# HBPB_FM_v4.net
KiCad netlist of a schematic drawn in EAGLE
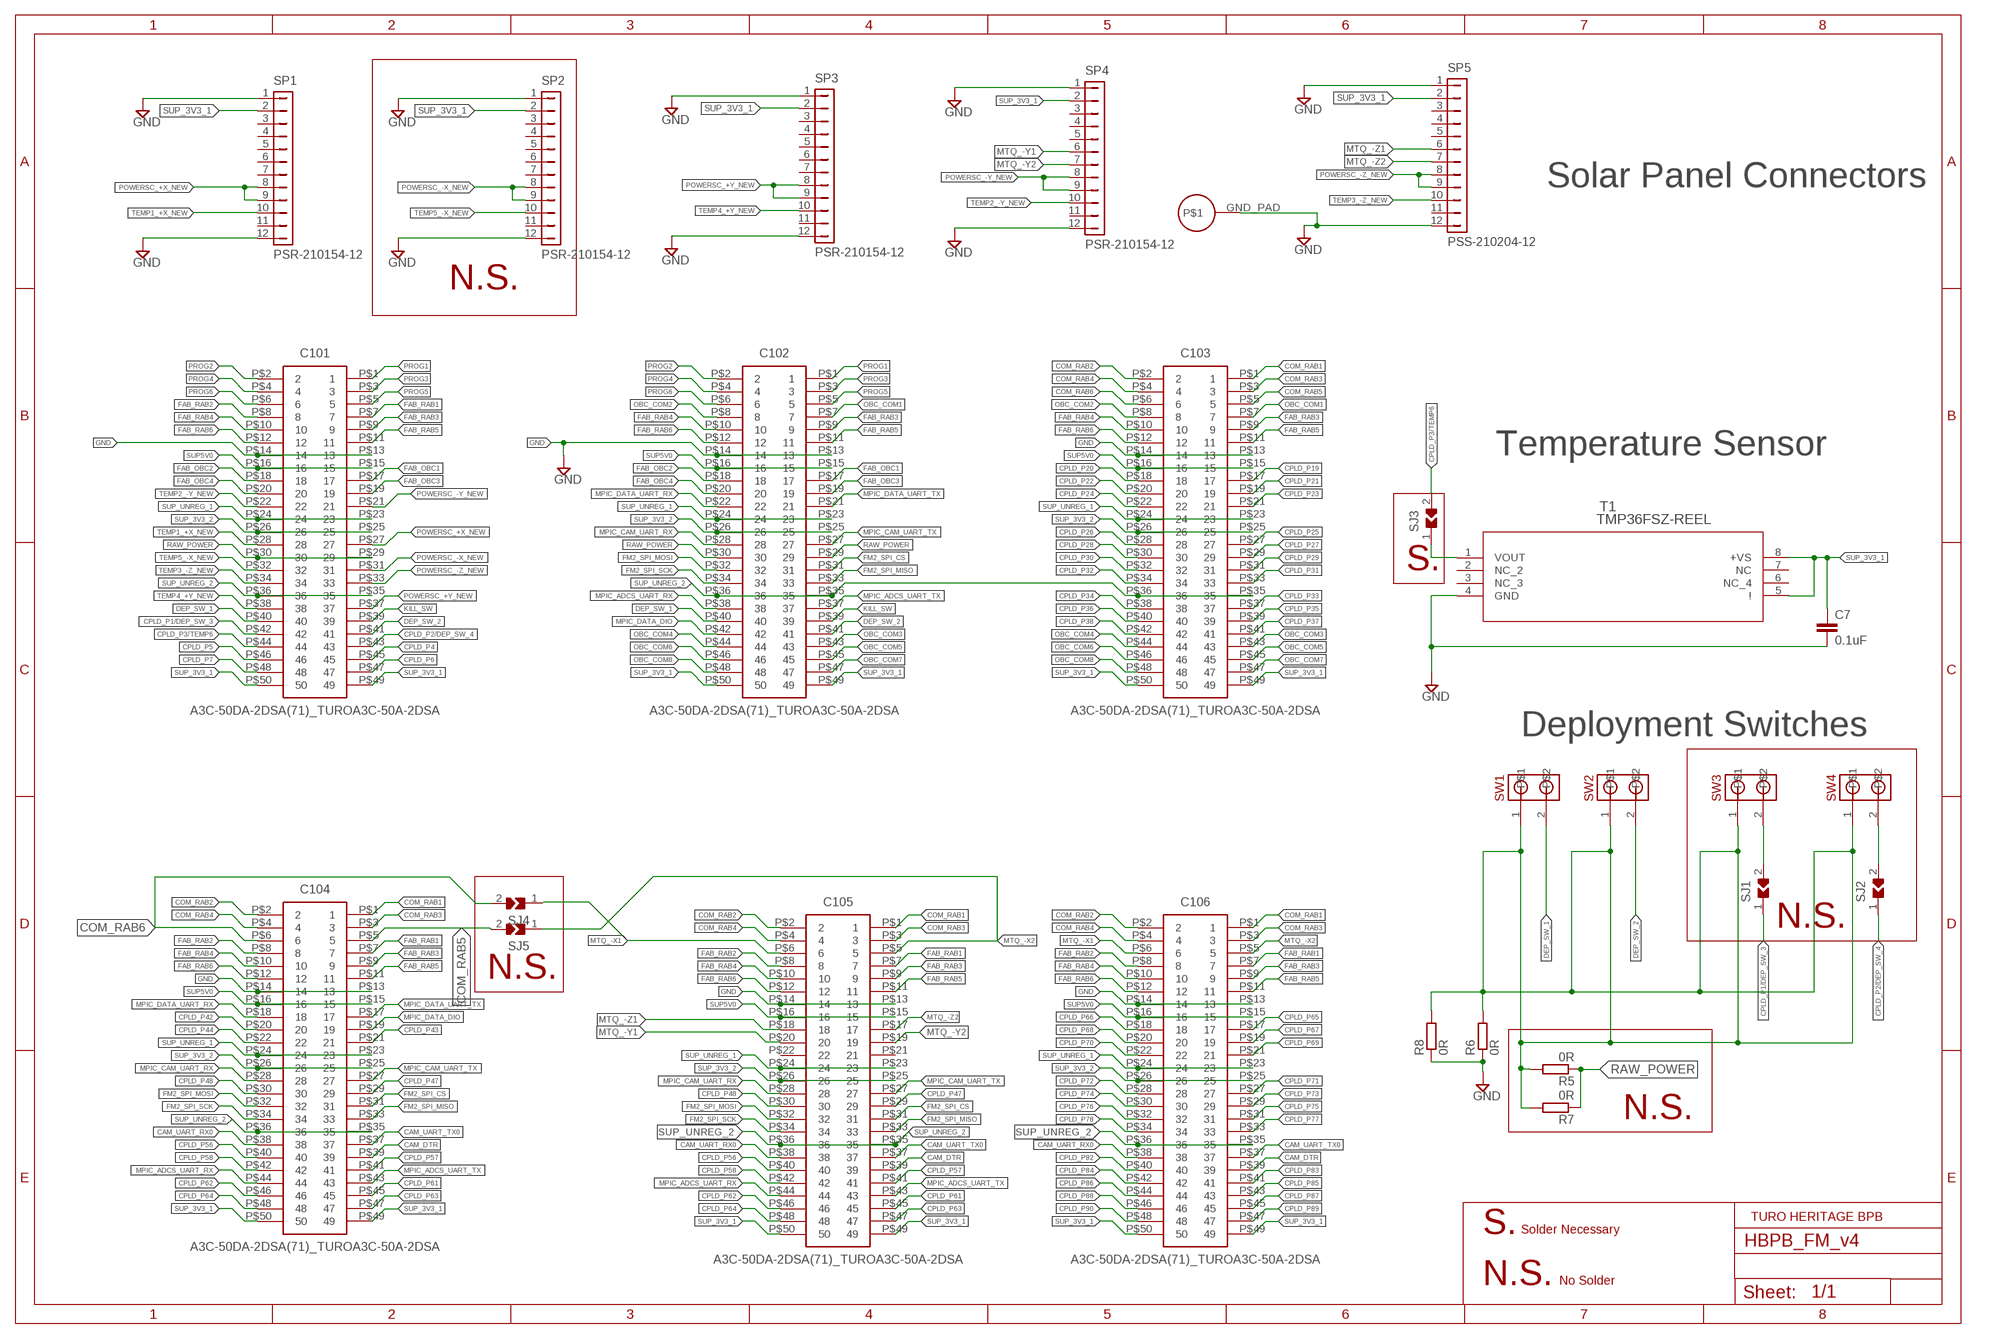
[diagram p0: schematic, sheet 1]

(export (version "E")
  (design (tool "Eeschema 10.0.6"))
  (components
    (comp (ref "C7")
      (value "0.1uF")
      (footprint "eagle-import:C0402")
      (libsource (lib "eagle-import") (part "CC0402"))
    )
    (comp (ref "C101")
      (value "A3C-50DA-2DSA(71)_TUROA3C-50A-2DSA")
      (footprint "eagle-import:SHDR50W60P200_2X25_5000X400X44_TR")
      (libsource (lib "eagle-import") (part "A3C-50DA-2DSA(71)_TUROA3C-50A-2DSA"))
    )
    (comp (ref "C102")
      (value "A3C-50DA-2DSA(71)_TUROA3C-50A-2DSA")
      (footprint "eagle-import:SHDR50W60P200_2X25_5000X400X44_TR")
      (libsource (lib "eagle-import") (part "A3C-50DA-2DSA(71)_TUROA3C-50A-2DSA"))
    )
    (comp (ref "C103")
      (value "A3C-50DA-2DSA(71)_TUROA3C-50A-2DSA")
      (footprint "eagle-import:SHDR50W60P200_2X25_5000X400X44_TR")
      (libsource (lib "eagle-import") (part "A3C-50DA-2DSA(71)_TUROA3C-50A-2DSA"))
    )
    (comp (ref "C104")
      (value "A3C-50DA-2DSA(71)_TUROA3C-50A-2DSA")
      (footprint "eagle-import:SHDR50W60P200_2X25_5000X400X44_TR")
      (libsource (lib "eagle-import") (part "A3C-50DA-2DSA(71)_TUROA3C-50A-2DSA"))
    )
    (comp (ref "C105")
      (value "A3C-50DA-2DSA(71)_TUROA3C-50A-2DSA")
      (footprint "eagle-import:SHDR50W60P200_2X25_5000X400X44_TR")
      (libsource (lib "eagle-import") (part "A3C-50DA-2DSA(71)_TUROA3C-50A-2DSA"))
    )
    (comp (ref "C106")
      (value "A3C-50DA-2DSA(71)_TUROA3C-50A-2DSA")
      (footprint "eagle-import:SHDR50W60P200_2X25_5000X400X44_TR")
      (libsource (lib "eagle-import") (part "A3C-50DA-2DSA(71)_TUROA3C-50A-2DSA"))
    )
    (comp (ref "R5")
      (value "0R")
      (footprint "eagle-import:R3216")
      (libsource (lib "eagle-import") (part "RR3216"))
    )
    (comp (ref "R6")
      (value "0R")
      (footprint "eagle-import:R3216")
      (libsource (lib "eagle-import") (part "RR3216"))
    )
    (comp (ref "R7")
      (value "0R")
      (footprint "eagle-import:R3216")
      (libsource (lib "eagle-import") (part "RR3216"))
    )
    (comp (ref "R8")
      (value "0R")
      (footprint "eagle-import:R3216")
      (libsource (lib "eagle-import") (part "RR3216"))
    )
    (comp (ref "SJ1")
      (value "SJ_BY_TURO")
      (footprint "eagle-import:SJ_TURO")
      (libsource (lib "eagle-import") (part "SJ_BY_TURO"))
    )
    (comp (ref "SJ2")
      (value "0R")
      (footprint "eagle-import:SJ_TURO")
      (libsource (lib "eagle-import") (part "SJ_BY_TURO"))
    )
    (comp (ref "SJ3")
      (value "SJ_BY_TURO")
      (footprint "eagle-import:SJ_TURO")
      (libsource (lib "eagle-import") (part "SJ_BY_TURO"))
    )
    (comp (ref "SJ4")
      (value "SJ_BY_TURO")
      (footprint "eagle-import:SJ_TURO")
      (libsource (lib "eagle-import") (part "SJ_BY_TURO"))
    )
    (comp (ref "SJ5")
      (value "SJ_BY_TURO")
      (footprint "eagle-import:SJ_TURO")
      (libsource (lib "eagle-import") (part "SJ_BY_TURO"))
    )
    (comp (ref "SP1")
      (value "PSR-210154-12")
      (footprint "eagle-import:PIN1X12_90")
      (libsource (lib "eagle-import") (part "PSR-210154-12"))
    )
    (comp (ref "SP2")
      (value "PSR-210154-12")
      (footprint "eagle-import:PIN1X12_90")
      (libsource (lib "eagle-import") (part "PSR-210154-12"))
    )
    (comp (ref "SP3")
      (value "PSR-210154-12")
      (footprint "eagle-import:PIN1X12_90")
      (libsource (lib "eagle-import") (part "PSR-210154-12"))
    )
    (comp (ref "SP4")
      (value "PSR-210154-12")
      (footprint "eagle-import:PIN1X12_90")
      (libsource (lib "eagle-import") (part "PSR-210154-12"))
    )
    (comp (ref "SP5")
      (value "PSS-210204-12")
      (footprint "eagle-import:PIN1X12")
      (libsource (lib "eagle-import") (part "PSS-210204-12"))
    )
    (comp (ref "SW1")
      (value "MOLEX-CONN-2-0554600272")
      (footprint "eagle-import:MOLEX-CONN-2-BIRDS")
      (libsource (lib "eagle-import") (part "MOLEX-CONN-2-0554600272"))
    )
    (comp (ref "SW2")
      (value "MOLEX-CONN-2-0554600272")
      (footprint "eagle-import:MOLEX-CONN-2-BIRDS")
      (libsource (lib "eagle-import") (part "MOLEX-CONN-2-0554600272"))
    )
    (comp (ref "SW3")
      (value "MOLEX-CONN-2-0554600272")
      (footprint "eagle-import:MOLEX-CONN-2-BIRDS")
      (libsource (lib "eagle-import") (part "MOLEX-CONN-2-0554600272"))
    )
    (comp (ref "SW4")
      (value "MOLEX-CONN-2-0554600272")
      (footprint "eagle-import:MOLEX-CONN-2-BIRDS")
      (libsource (lib "eagle-import") (part "MOLEX-CONN-2-0554600272"))
    )
    (comp (ref "T1")
      (value "TMP36FSZ-REEL")
      (footprint "eagle-import:R_8")
      (fields (field (name "MANUFACTURER_PART_NUMBER") "TMP36FSZREEL"))
      (libsource (lib "eagle-import") (part "TMP36FSZ-REEL"))
    )
    (comp (ref "U$1")
      (value "GND_PAD")
      (footprint "eagle-import:GND_PAD")
      (libsource (lib "eagle-import") (part "GND_PAD"))
    )
  )
  (nets
    (net (code "1") (name "CAM_DTR") (class "Default")
      (node (ref "C104") (pin "P$39") (pinfunction "39_P$39") (pintype "passive"))
      (node (ref "C105") (pin "P$39") (pinfunction "39_P$39") (pintype "passive"))
      (node (ref "C106") (pin "P$39") (pinfunction "39_P$39") (pintype "passive"))
    )
    (net (code "2") (name "CAM_UART_RX0") (class "Default")
      (node (ref "C104") (pin "P$38") (pinfunction "38_P$38") (pintype "passive"))
      (node (ref "C105") (pin "P$38") (pinfunction "38_P$38") (pintype "passive"))
      (node (ref "C106") (pin "P$38") (pinfunction "38_P$38") (pintype "passive"))
    )
    (net (code "3") (name "CAM_UART_TX0") (class "Default")
      (node (ref "C104") (pin "P$37") (pinfunction "37_P$37") (pintype "passive"))
      (node (ref "C105") (pin "P$37") (pinfunction "37_P$37") (pintype "passive"))
      (node (ref "C106") (pin "P$37") (pinfunction "37_P$37") (pintype "passive"))
    )
    (net (code "4") (name "COM_RAB1") (class "Default")
      (node (ref "C103") (pin "P$1") (pinfunction "1_P$1") (pintype "passive"))
      (node (ref "C104") (pin "P$1") (pinfunction "1_P$1") (pintype "passive"))
      (node (ref "C105") (pin "P$1") (pinfunction "1_P$1") (pintype "passive"))
      (node (ref "C106") (pin "P$1") (pinfunction "1_P$1") (pintype "passive"))
    )
    (net (code "5") (name "COM_RAB2") (class "Default")
      (node (ref "C103") (pin "P$2") (pinfunction "2_P$2") (pintype "passive"))
      (node (ref "C104") (pin "P$2") (pinfunction "2_P$2") (pintype "passive"))
      (node (ref "C105") (pin "P$2") (pinfunction "2_P$2") (pintype "passive"))
      (node (ref "C106") (pin "P$2") (pinfunction "2_P$2") (pintype "passive"))
    )
    (net (code "6") (name "COM_RAB3") (class "Default")
      (node (ref "C103") (pin "P$3") (pinfunction "3_P$3") (pintype "passive"))
      (node (ref "C104") (pin "P$3") (pinfunction "3_P$3") (pintype "passive"))
      (node (ref "C105") (pin "P$3") (pinfunction "3_P$3") (pintype "passive"))
      (node (ref "C106") (pin "P$3") (pinfunction "3_P$3") (pintype "passive"))
    )
    (net (code "7") (name "COM_RAB4") (class "Default")
      (node (ref "C103") (pin "P$4") (pinfunction "4_P$4") (pintype "passive"))
      (node (ref "C104") (pin "P$4") (pinfunction "4_P$4") (pintype "passive"))
      (node (ref "C105") (pin "P$4") (pinfunction "4_P$4") (pintype "passive"))
      (node (ref "C106") (pin "P$4") (pinfunction "4_P$4") (pintype "passive"))
    )
    (net (code "8") (name "COM_RAB5") (class "Default")
      (node (ref "C103") (pin "P$5") (pinfunction "5_P$5") (pintype "passive"))
      (node (ref "C104") (pin "P$5") (pinfunction "5_P$5") (pintype "passive"))
      (node (ref "SJ5") (pin "2") (pinfunction "2_2") (pintype "passive"))
    )
    (net (code "9") (name "COM_RAB6") (class "Default")
      (node (ref "C103") (pin "P$6") (pinfunction "6_P$6") (pintype "passive"))
      (node (ref "C104") (pin "P$6") (pinfunction "6_P$6") (pintype "passive"))
      (node (ref "SJ4") (pin "2") (pinfunction "2_2") (pintype "passive"))
    )
    (net (code "10") (name "CPLD_P1{slash}DEP_SW_3") (class "Default")
      (node (ref "C101") (pin "P$42") (pinfunction "42_P$42") (pintype "passive"))
      (node (ref "SJ1") (pin "1") (pinfunction "1_1") (pintype "passive"))
    )
    (net (code "11") (name "CPLD_P2{slash}DEP_SW_4") (class "Default")
      (node (ref "C101") (pin "P$43") (pinfunction "43_P$43") (pintype "passive"))
      (node (ref "SJ2") (pin "1") (pinfunction "1_1") (pintype "passive"))
    )
    (net (code "12") (name "CPLD_P3{slash}TEMP6") (class "Default")
      (node (ref "C101") (pin "P$44") (pinfunction "44_P$44") (pintype "passive"))
      (node (ref "SJ3") (pin "2") (pinfunction "2_2") (pintype "passive"))
    )
    (net (code "13") (name "CPLD_P4") (class "Default")
      (node (ref "C101") (pin "P$45") (pinfunction "45_P$45") (pintype "passive"))
    )
    (net (code "14") (name "CPLD_P5") (class "Default")
      (node (ref "C101") (pin "P$46") (pinfunction "46_P$46") (pintype "passive"))
    )
    (net (code "15") (name "CPLD_P6") (class "Default")
      (node (ref "C101") (pin "P$47") (pinfunction "47_P$47") (pintype "passive"))
    )
    (net (code "16") (name "CPLD_P7") (class "Default")
      (node (ref "C101") (pin "P$48") (pinfunction "48_P$48") (pintype "passive"))
    )
    (net (code "17") (name "CPLD_P19") (class "Default")
      (node (ref "C103") (pin "P$17") (pinfunction "17_P$17") (pintype "passive"))
    )
    (net (code "18") (name "CPLD_P20") (class "Default")
      (node (ref "C103") (pin "P$18") (pinfunction "18_P$18") (pintype "passive"))
    )
    (net (code "19") (name "CPLD_P21") (class "Default")
      (node (ref "C103") (pin "P$19") (pinfunction "19_P$19") (pintype "passive"))
    )
    (net (code "20") (name "CPLD_P22") (class "Default")
      (node (ref "C103") (pin "P$20") (pinfunction "20_P$20") (pintype "passive"))
    )
    (net (code "21") (name "CPLD_P23") (class "Default")
      (node (ref "C103") (pin "P$21") (pinfunction "21_P$21") (pintype "passive"))
    )
    (net (code "22") (name "CPLD_P24") (class "Default")
      (node (ref "C103") (pin "P$22") (pinfunction "22_P$22") (pintype "passive"))
    )
    (net (code "23") (name "CPLD_P25") (class "Default")
      (node (ref "C103") (pin "P$27") (pinfunction "27_P$27") (pintype "passive"))
    )
    (net (code "24") (name "CPLD_P26") (class "Default")
      (node (ref "C103") (pin "P$28") (pinfunction "28_P$28") (pintype "passive"))
    )
    (net (code "25") (name "CPLD_P27") (class "Default")
      (node (ref "C103") (pin "P$29") (pinfunction "29_P$29") (pintype "passive"))
    )
    (net (code "26") (name "CPLD_P28") (class "Default")
      (node (ref "C103") (pin "P$30") (pinfunction "30_P$30") (pintype "passive"))
    )
    (net (code "27") (name "CPLD_P29") (class "Default")
      (node (ref "C103") (pin "P$31") (pinfunction "31_P$31") (pintype "passive"))
    )
    (net (code "28") (name "CPLD_P30") (class "Default")
      (node (ref "C103") (pin "P$32") (pinfunction "32_P$32") (pintype "passive"))
    )
    (net (code "29") (name "CPLD_P31") (class "Default")
      (node (ref "C103") (pin "P$33") (pinfunction "33_P$33") (pintype "passive"))
    )
    (net (code "30") (name "CPLD_P32") (class "Default")
      (node (ref "C103") (pin "P$34") (pinfunction "34_P$34") (pintype "passive"))
    )
    (net (code "31") (name "CPLD_P33") (class "Default")
      (node (ref "C103") (pin "P$37") (pinfunction "37_P$37") (pintype "passive"))
    )
    (net (code "32") (name "CPLD_P34") (class "Default")
      (node (ref "C103") (pin "P$38") (pinfunction "38_P$38") (pintype "passive"))
    )
    (net (code "33") (name "CPLD_P35") (class "Default")
      (node (ref "C103") (pin "P$39") (pinfunction "39_P$39") (pintype "passive"))
    )
    (net (code "34") (name "CPLD_P36") (class "Default")
      (node (ref "C103") (pin "P$40") (pinfunction "40_P$40") (pintype "passive"))
    )
    (net (code "35") (name "CPLD_P37") (class "Default")
      (node (ref "C103") (pin "P$41") (pinfunction "41_P$41") (pintype "passive"))
    )
    (net (code "36") (name "CPLD_P38") (class "Default")
      (node (ref "C103") (pin "P$42") (pinfunction "42_P$42") (pintype "passive"))
    )
    (net (code "37") (name "CPLD_P42") (class "Default")
      (node (ref "C104") (pin "P$20") (pinfunction "20_P$20") (pintype "passive"))
    )
    (net (code "38") (name "CPLD_P43") (class "Default")
      (node (ref "C104") (pin "P$21") (pinfunction "21_P$21") (pintype "passive"))
    )
    (net (code "39") (name "CPLD_P44") (class "Default")
      (node (ref "C104") (pin "P$22") (pinfunction "22_P$22") (pintype "passive"))
    )
    (net (code "40") (name "CPLD_P47") (class "Default")
      (node (ref "C104") (pin "P$29") (pinfunction "29_P$29") (pintype "passive"))
      (node (ref "C105") (pin "P$29") (pinfunction "29_P$29") (pintype "passive"))
    )
    (net (code "41") (name "CPLD_P48") (class "Default")
      (node (ref "C104") (pin "P$30") (pinfunction "30_P$30") (pintype "passive"))
      (node (ref "C105") (pin "P$30") (pinfunction "30_P$30") (pintype "passive"))
    )
    (net (code "42") (name "CPLD_P56") (class "Default")
      (node (ref "C104") (pin "P$40") (pinfunction "40_P$40") (pintype "passive"))
      (node (ref "C105") (pin "P$40") (pinfunction "40_P$40") (pintype "passive"))
    )
    (net (code "43") (name "CPLD_P57") (class "Default")
      (node (ref "C104") (pin "P$41") (pinfunction "41_P$41") (pintype "passive"))
      (node (ref "C105") (pin "P$41") (pinfunction "41_P$41") (pintype "passive"))
    )
    (net (code "44") (name "CPLD_P58") (class "Default")
      (node (ref "C104") (pin "P$42") (pinfunction "42_P$42") (pintype "passive"))
      (node (ref "C105") (pin "P$42") (pinfunction "42_P$42") (pintype "passive"))
    )
    (net (code "45") (name "CPLD_P61") (class "Default")
      (node (ref "C104") (pin "P$45") (pinfunction "45_P$45") (pintype "passive"))
      (node (ref "C105") (pin "P$45") (pinfunction "45_P$45") (pintype "passive"))
    )
    (net (code "46") (name "CPLD_P62") (class "Default")
      (node (ref "C104") (pin "P$46") (pinfunction "46_P$46") (pintype "passive"))
      (node (ref "C105") (pin "P$46") (pinfunction "46_P$46") (pintype "passive"))
    )
    (net (code "47") (name "CPLD_P63") (class "Default")
      (node (ref "C104") (pin "P$47") (pinfunction "47_P$47") (pintype "passive"))
      (node (ref "C105") (pin "P$47") (pinfunction "47_P$47") (pintype "passive"))
    )
    (net (code "48") (name "CPLD_P64") (class "Default")
      (node (ref "C104") (pin "P$48") (pinfunction "48_P$48") (pintype "passive"))
      (node (ref "C105") (pin "P$48") (pinfunction "48_P$48") (pintype "passive"))
    )
    (net (code "49") (name "CPLD_P65") (class "Default")
      (node (ref "C106") (pin "P$17") (pinfunction "17_P$17") (pintype "passive"))
    )
    (net (code "50") (name "CPLD_P66") (class "Default")
      (node (ref "C106") (pin "P$18") (pinfunction "18_P$18") (pintype "passive"))
    )
    (net (code "51") (name "CPLD_P67") (class "Default")
      (node (ref "C106") (pin "P$19") (pinfunction "19_P$19") (pintype "passive"))
    )
    (net (code "52") (name "CPLD_P68") (class "Default")
      (node (ref "C106") (pin "P$20") (pinfunction "20_P$20") (pintype "passive"))
    )
    (net (code "53") (name "CPLD_P69") (class "Default")
      (node (ref "C106") (pin "P$21") (pinfunction "21_P$21") (pintype "passive"))
    )
    (net (code "54") (name "CPLD_P70") (class "Default")
      (node (ref "C106") (pin "P$22") (pinfunction "22_P$22") (pintype "passive"))
    )
    (net (code "55") (name "CPLD_P71") (class "Default")
      (node (ref "C106") (pin "P$27") (pinfunction "27_P$27") (pintype "passive"))
    )
    (net (code "56") (name "CPLD_P72") (class "Default")
      (node (ref "C106") (pin "P$28") (pinfunction "28_P$28") (pintype "passive"))
    )
    (net (code "57") (name "CPLD_P73") (class "Default")
      (node (ref "C106") (pin "P$29") (pinfunction "29_P$29") (pintype "passive"))
    )
    (net (code "58") (name "CPLD_P74") (class "Default")
      (node (ref "C106") (pin "P$30") (pinfunction "30_P$30") (pintype "passive"))
    )
    (net (code "59") (name "CPLD_P75") (class "Default")
      (node (ref "C106") (pin "P$31") (pinfunction "31_P$31") (pintype "passive"))
    )
    (net (code "60") (name "CPLD_P76") (class "Default")
      (node (ref "C106") (pin "P$32") (pinfunction "32_P$32") (pintype "passive"))
    )
    (net (code "61") (name "CPLD_P77") (class "Default")
      (node (ref "C106") (pin "P$33") (pinfunction "33_P$33") (pintype "passive"))
    )
    (net (code "62") (name "CPLD_P78") (class "Default")
      (node (ref "C106") (pin "P$34") (pinfunction "34_P$34") (pintype "passive"))
    )
    (net (code "63") (name "CPLD_P82") (class "Default")
      (node (ref "C106") (pin "P$40") (pinfunction "40_P$40") (pintype "passive"))
    )
    (net (code "64") (name "CPLD_P83") (class "Default")
      (node (ref "C106") (pin "P$41") (pinfunction "41_P$41") (pintype "passive"))
    )
    (net (code "65") (name "CPLD_P84") (class "Default")
      (node (ref "C106") (pin "P$42") (pinfunction "42_P$42") (pintype "passive"))
    )
    (net (code "66") (name "CPLD_P85") (class "Default")
      (node (ref "C106") (pin "P$43") (pinfunction "43_P$43") (pintype "passive"))
    )
    (net (code "67") (name "CPLD_P86") (class "Default")
      (node (ref "C106") (pin "P$44") (pinfunction "44_P$44") (pintype "passive"))
    )
    (net (code "68") (name "CPLD_P87") (class "Default")
      (node (ref "C106") (pin "P$45") (pinfunction "45_P$45") (pintype "passive"))
    )
    (net (code "69") (name "CPLD_P88") (class "Default")
      (node (ref "C106") (pin "P$46") (pinfunction "46_P$46") (pintype "passive"))
    )
    (net (code "70") (name "CPLD_P89") (class "Default")
      (node (ref "C106") (pin "P$47") (pinfunction "47_P$47") (pintype "passive"))
    )
    (net (code "71") (name "CPLD_P90") (class "Default")
      (node (ref "C106") (pin "P$48") (pinfunction "48_P$48") (pintype "passive"))
    )
    (net (code "72") (name "DEP_SW_1") (class "Default")
      (node (ref "C101") (pin "P$40") (pinfunction "40_P$40") (pintype "passive"))
      (node (ref "C102") (pin "P$40") (pinfunction "40_P$40") (pintype "passive"))
      (node (ref "SW1") (pin "2") (pinfunction "P$2_2") (pintype "bidirectional"))
    )
    (net (code "73") (name "DEP_SW_2") (class "Default")
      (node (ref "C101") (pin "P$41") (pinfunction "41_P$41") (pintype "passive"))
      (node (ref "C102") (pin "P$41") (pinfunction "41_P$41") (pintype "passive"))
      (node (ref "SW2") (pin "2") (pinfunction "P$2_2") (pintype "bidirectional"))
    )
    (net (code "74") (name "FAB_OBC1") (class "Default")
      (node (ref "C101") (pin "P$17") (pinfunction "17_P$17") (pintype "passive"))
      (node (ref "C102") (pin "P$17") (pinfunction "17_P$17") (pintype "passive"))
    )
    (net (code "75") (name "FAB_OBC2") (class "Default")
      (node (ref "C101") (pin "P$18") (pinfunction "18_P$18") (pintype "passive"))
      (node (ref "C102") (pin "P$18") (pinfunction "18_P$18") (pintype "passive"))
    )
    (net (code "76") (name "FAB_OBC3") (class "Default")
      (node (ref "C101") (pin "P$19") (pinfunction "19_P$19") (pintype "passive"))
      (node (ref "C102") (pin "P$19") (pinfunction "19_P$19") (pintype "passive"))
    )
    (net (code "77") (name "FAB_OBC4") (class "Default")
      (node (ref "C101") (pin "P$20") (pinfunction "20_P$20") (pintype "passive"))
      (node (ref "C102") (pin "P$20") (pinfunction "20_P$20") (pintype "passive"))
    )
    (net (code "78") (name "FAB_RAB1") (class "Default")
      (node (ref "C101") (pin "P$7") (pinfunction "7_P$7") (pintype "passive"))
      (node (ref "C104") (pin "P$7") (pinfunction "7_P$7") (pintype "passive"))
      (node (ref "C105") (pin "P$7") (pinfunction "7_P$7") (pintype "passive"))
      (node (ref "C106") (pin "P$7") (pinfunction "7_P$7") (pintype "passive"))
    )
    (net (code "79") (name "FAB_RAB2") (class "Default")
      (node (ref "C101") (pin "P$8") (pinfunction "8_P$8") (pintype "passive"))
      (node (ref "C104") (pin "P$8") (pinfunction "8_P$8") (pintype "passive"))
      (node (ref "C105") (pin "P$8") (pinfunction "8_P$8") (pintype "passive"))
      (node (ref "C106") (pin "P$8") (pinfunction "8_P$8") (pintype "passive"))
    )
    (net (code "80") (name "FAB_RAB3") (class "Default")
      (node (ref "C101") (pin "P$9") (pinfunction "9_P$9") (pintype "passive"))
      (node (ref "C102") (pin "P$9") (pinfunction "9_P$9") (pintype "passive"))
      (node (ref "C103") (pin "P$9") (pinfunction "9_P$9") (pintype "passive"))
      (node (ref "C104") (pin "P$9") (pinfunction "9_P$9") (pintype "passive"))
      (node (ref "C105") (pin "P$9") (pinfunction "9_P$9") (pintype "passive"))
      (node (ref "C106") (pin "P$9") (pinfunction "9_P$9") (pintype "passive"))
    )
    (net (code "81") (name "FAB_RAB4") (class "Default")
      (node (ref "C101") (pin "P$10") (pinfunction "10_P$10") (pintype "passive"))
      (node (ref "C102") (pin "P$10") (pinfunction "10_P$10") (pintype "passive"))
      (node (ref "C103") (pin "P$10") (pinfunction "10_P$10") (pintype "passive"))
      (node (ref "C104") (pin "P$10") (pinfunction "10_P$10") (pintype "passive"))
      (node (ref "C105") (pin "P$10") (pinfunction "10_P$10") (pintype "passive"))
      (node (ref "C106") (pin "P$10") (pinfunction "10_P$10") (pintype "passive"))
    )
    (net (code "82") (name "FAB_RAB5") (class "Default")
      (node (ref "C101") (pin "P$11") (pinfunction "11_P$11") (pintype "passive"))
      (node (ref "C102") (pin "P$11") (pinfunction "11_P$11") (pintype "passive"))
      (node (ref "C103") (pin "P$11") (pinfunction "11_P$11") (pintype "passive"))
      (node (ref "C104") (pin "P$11") (pinfunction "11_P$11") (pintype "passive"))
      (node (ref "C105") (pin "P$11") (pinfunction "11_P$11") (pintype "passive"))
      (node (ref "C106") (pin "P$11") (pinfunction "11_P$11") (pintype "passive"))
    )
    (net (code "83") (name "FAB_RAB6") (class "Default")
      (node (ref "C101") (pin "P$12") (pinfunction "12_P$12") (pintype "passive"))
      (node (ref "C102") (pin "P$12") (pinfunction "12_P$12") (pintype "passive"))
      (node (ref "C103") (pin "P$12") (pinfunction "12_P$12") (pintype "passive"))
      (node (ref "C104") (pin "P$12") (pinfunction "12_P$12") (pintype "passive"))
      (node (ref "C105") (pin "P$12") (pinfunction "12_P$12") (pintype "passive"))
      (node (ref "C106") (pin "P$12") (pinfunction "12_P$12") (pintype "passive"))
    )
    (net (code "84") (name "FM2_SPI_CS") (class "Default")
      (node (ref "C102") (pin "P$31") (pinfunction "31_P$31") (pintype "passive"))
      (node (ref "C104") (pin "P$31") (pinfunction "31_P$31") (pintype "passive"))
      (node (ref "C105") (pin "P$31") (pinfunction "31_P$31") (pintype "passive"))
    )
    (net (code "85") (name "FM2_SPI_MISO") (class "Default")
      (node (ref "C102") (pin "P$33") (pinfunction "33_P$33") (pintype "passive"))
      (node (ref "C104") (pin "P$33") (pinfunction "33_P$33") (pintype "passive"))
      (node (ref "C105") (pin "P$33") (pinfunction "33_P$33") (pintype "passive"))
    )
    (net (code "86") (name "FM2_SPI_MOSI") (class "Default")
      (node (ref "C102") (pin "P$32") (pinfunction "32_P$32") (pintype "passive"))
      (node (ref "C104") (pin "P$32") (pinfunction "32_P$32") (pintype "passive"))
      (node (ref "C105") (pin "P$32") (pinfunction "32_P$32") (pintype "passive"))
    )
    (net (code "87") (name "FM2_SPI_SCK") (class "Default")
      (node (ref "C102") (pin "P$34") (pinfunction "34_P$34") (pintype "passive"))
      (node (ref "C104") (pin "P$34") (pinfunction "34_P$34") (pintype "passive"))
      (node (ref "C105") (pin "P$34") (pinfunction "34_P$34") (pintype "passive"))
    )
    (net (code "88") (name "GND") (class "Default")
      (node (ref "C101") (pin "P$13") (pinfunction "13_P$13") (pintype "passive"))
      (node (ref "C101") (pin "P$14") (pinfunction "14_P$14") (pintype "passive"))
      (node (ref "C102") (pin "P$13") (pinfunction "13_P$13") (pintype "passive"))
      (node (ref "C102") (pin "P$14") (pinfunction "14_P$14") (pintype "passive"))
      (node (ref "C103") (pin "P$13") (pinfunction "13_P$13") (pintype "passive"))
      (node (ref "C103") (pin "P$14") (pinfunction "14_P$14") (pintype "passive"))
      (node (ref "C104") (pin "P$13") (pinfunction "13_P$13") (pintype "passive"))
      (node (ref "C104") (pin "P$14") (pinfunction "14_P$14") (pintype "passive"))
      (node (ref "C105") (pin "P$13") (pinfunction "13_P$13") (pintype "passive"))
      (node (ref "C105") (pin "P$14") (pinfunction "14_P$14") (pintype "passive"))
      (node (ref "C106") (pin "P$13") (pinfunction "13_P$13") (pintype "passive"))
      (node (ref "C106") (pin "P$14") (pinfunction "14_P$14") (pintype "passive"))
      (node (ref "C7") (pin "2") (pinfunction "2_2") (pintype "passive"))
      (node (ref "R6") (pin "1") (pinfunction "1_1") (pintype "passive"))
      (node (ref "R8") (pin "1") (pinfunction "1_1") (pintype "passive"))
      (node (ref "SP1") (pin "1") (pinfunction "1_1") (pintype "passive"))
      (node (ref "SP1") (pin "12") (pinfunction "12_12") (pintype "passive"))
      (node (ref "SP2") (pin "1") (pinfunction "1_1") (pintype "passive"))
      (node (ref "SP2") (pin "12") (pinfunction "12_12") (pintype "passive"))
      (node (ref "SP3") (pin "1") (pinfunction "1_1") (pintype "passive"))
      (node (ref "SP3") (pin "12") (pinfunction "12_12") (pintype "passive"))
      (node (ref "SP4") (pin "1") (pinfunction "1_1") (pintype "passive"))
      (node (ref "SP4") (pin "12") (pinfunction "12_12") (pintype "passive"))
      (node (ref "SP5") (pin "1") (pinfunction "1_1") (pintype "passive"))
      (node (ref "SP5") (pin "12") (pinfunction "12_12") (pintype "passive"))
      (node (ref "T1") (pin "4") (pinfunction "GND_4") (pintype "passive"))
      (node (ref "U$1") (pin "GND_PAD") (pinfunction "P$1_GND_PAD") (pintype "bidirectional"))
    )
    (net (code "89") (name "KILL_SW") (class "Default")
      (node (ref "C101") (pin "P$39") (pinfunction "39_P$39") (pintype "passive"))
      (node (ref "C102") (pin "P$39") (pinfunction "39_P$39") (pintype "passive"))
    )
    (net (code "90") (name "MPIC_ADCS_UART_RX") (class "Default")
      (node (ref "C102") (pin "P$38") (pinfunction "38_P$38") (pintype "passive"))
      (node (ref "C104") (pin "P$44") (pinfunction "44_P$44") (pintype "passive"))
      (node (ref "C105") (pin "P$44") (pinfunction "44_P$44") (pintype "passive"))
    )
    (net (code "91") (name "MPIC_ADCS_UART_TX") (class "Default")
      (node (ref "C102") (pin "P$37") (pinfunction "37_P$37") (pintype "passive"))
      (node (ref "C104") (pin "P$43") (pinfunction "43_P$43") (pintype "passive"))
      (node (ref "C105") (pin "P$43") (pinfunction "43_P$43") (pintype "passive"))
    )
    (net (code "92") (name "MPIC_CAM_UART_RX") (class "Default")
      (node (ref "C102") (pin "P$28") (pinfunction "28_P$28") (pintype "passive"))
      (node (ref "C104") (pin "P$28") (pinfunction "28_P$28") (pintype "passive"))
      (node (ref "C105") (pin "P$28") (pinfunction "28_P$28") (pintype "passive"))
    )
    (net (code "93") (name "MPIC_CAM_UART_TX") (class "Default")
      (node (ref "C102") (pin "P$27") (pinfunction "27_P$27") (pintype "passive"))
      (node (ref "C104") (pin "P$27") (pinfunction "27_P$27") (pintype "passive"))
      (node (ref "C105") (pin "P$27") (pinfunction "27_P$27") (pintype "passive"))
    )
    (net (code "94") (name "MPIC_DATA_DIO") (class "Default")
      (node (ref "C102") (pin "P$42") (pinfunction "42_P$42") (pintype "passive"))
      (node (ref "C104") (pin "P$19") (pinfunction "19_P$19") (pintype "passive"))
    )
    (net (code "95") (name "MPIC_DATA_UART_RX") (class "Default")
      (node (ref "C102") (pin "P$22") (pinfunction "22_P$22") (pintype "passive"))
      (node (ref "C104") (pin "P$18") (pinfunction "18_P$18") (pintype "passive"))
    )
    (net (code "96") (name "MPIC_DATA_UART_TX") (class "Default")
      (node (ref "C102") (pin "P$21") (pinfunction "21_P$21") (pintype "passive"))
      (node (ref "C104") (pin "P$17") (pinfunction "17_P$17") (pintype "passive"))
    )
    (net (code "97") (name "MTQ_-X1") (class "Default")
      (node (ref "C105") (pin "P$6") (pinfunction "6_P$6") (pintype "passive"))
      (node (ref "C106") (pin "P$6") (pinfunction "6_P$6") (pintype "passive"))
      (node (ref "SJ4") (pin "1") (pinfunction "1_1") (pintype "passive"))
    )
    (net (code "98") (name "MTQ_-X2") (class "Default")
      (node (ref "C105") (pin "P$5") (pinfunction "5_P$5") (pintype "passive"))
      (node (ref "C106") (pin "P$5") (pinfunction "5_P$5") (pintype "passive"))
      (node (ref "SJ5") (pin "1") (pinfunction "1_1") (pintype "passive"))
    )
    (net (code "99") (name "MTQ_-Y1") (class "Default")
      (node (ref "C105") (pin "P$20") (pinfunction "20_P$20") (pintype "passive"))
      (node (ref "SP4") (pin "6") (pinfunction "6_6") (pintype "passive"))
    )
    (net (code "100") (name "MTQ_-Y2") (class "Default")
      (node (ref "C105") (pin "P$19") (pinfunction "19_P$19") (pintype "passive"))
      (node (ref "SP4") (pin "7") (pinfunction "7_7") (pintype "passive"))
    )
    (net (code "101") (name "MTQ_-Z1") (class "Default")
      (node (ref "C105") (pin "P$18") (pinfunction "18_P$18") (pintype "passive"))
      (node (ref "SP5") (pin "6") (pinfunction "6_6") (pintype "passive"))
    )
    (net (code "102") (name "MTQ_-Z2") (class "Default")
      (node (ref "C105") (pin "P$17") (pinfunction "17_P$17") (pintype "passive"))
      (node (ref "SP5") (pin "7") (pinfunction "7_7") (pintype "passive"))
    )
    (net (code "103") (name "Net-(SW1-P$1)") (class "Default")
      (node (ref "R5") (pin "2") (pinfunction "2_2") (pintype "passive"))
      (node (ref "R6") (pin "2") (pinfunction "2_2") (pintype "passive"))
      (node (ref "R7") (pin "2") (pinfunction "2_2") (pintype "passive"))
      (node (ref "R8") (pin "2") (pinfunction "2_2") (pintype "passive"))
      (node (ref "SW1") (pin "1") (pinfunction "P$1_1") (pintype "bidirectional"))
      (node (ref "SW2") (pin "1") (pinfunction "P$1_1") (pintype "bidirectional"))
      (node (ref "SW3") (pin "1") (pinfunction "P$1_1") (pintype "bidirectional"))
      (node (ref "SW4") (pin "1") (pinfunction "P$1_1") (pintype "bidirectional"))
    )
    (net (code "104") (name "Net-(SW3-P$2)") (class "Default")
      (node (ref "SJ1") (pin "2") (pinfunction "2_2") (pintype "passive"))
      (node (ref "SW3") (pin "2") (pinfunction "P$2_2") (pintype "bidirectional"))
    )
    (net (code "105") (name "Net-(SW4-P$2)") (class "Default")
      (node (ref "SJ2") (pin "2") (pinfunction "2_2") (pintype "passive"))
      (node (ref "SW4") (pin "2") (pinfunction "P$2_2") (pintype "bidirectional"))
    )
    (net (code "106") (name "Net-(T1-VOUT)") (class "Default")
      (node (ref "SJ3") (pin "1") (pinfunction "1_1") (pintype "passive"))
      (node (ref "T1") (pin "1") (pinfunction "VOUT_1") (pintype "passive"))
    )
    (net (code "107") (name "OBC_COM1") (class "Default")
      (node (ref "C102") (pin "P$7") (pinfunction "7_P$7") (pintype "passive"))
      (node (ref "C103") (pin "P$7") (pinfunction "7_P$7") (pintype "passive"))
    )
    (net (code "108") (name "OBC_COM2") (class "Default")
      (node (ref "C102") (pin "P$8") (pinfunction "8_P$8") (pintype "passive"))
      (node (ref "C103") (pin "P$8") (pinfunction "8_P$8") (pintype "passive"))
    )
    (net (code "109") (name "OBC_COM3") (class "Default")
      (node (ref "C102") (pin "P$43") (pinfunction "43_P$43") (pintype "passive"))
      (node (ref "C103") (pin "P$43") (pinfunction "43_P$43") (pintype "passive"))
    )
    (net (code "110") (name "OBC_COM4") (class "Default")
      (node (ref "C102") (pin "P$44") (pinfunction "44_P$44") (pintype "passive"))
      (node (ref "C103") (pin "P$44") (pinfunction "44_P$44") (pintype "passive"))
    )
    (net (code "111") (name "OBC_COM5") (class "Default")
      (node (ref "C102") (pin "P$45") (pinfunction "45_P$45") (pintype "passive"))
      (node (ref "C103") (pin "P$45") (pinfunction "45_P$45") (pintype "passive"))
    )
    (net (code "112") (name "OBC_COM6") (class "Default")
      (node (ref "C102") (pin "P$46") (pinfunction "46_P$46") (pintype "passive"))
      (node (ref "C103") (pin "P$46") (pinfunction "46_P$46") (pintype "passive"))
    )
    (net (code "113") (name "OBC_COM7") (class "Default")
      (node (ref "C102") (pin "P$47") (pinfunction "47_P$47") (pintype "passive"))
      (node (ref "C103") (pin "P$47") (pinfunction "47_P$47") (pintype "passive"))
    )
    (net (code "114") (name "OBC_COM8") (class "Default")
      (node (ref "C102") (pin "P$48") (pinfunction "48_P$48") (pintype "passive"))
      (node (ref "C103") (pin "P$48") (pinfunction "48_P$48") (pintype "passive"))
    )
    (net (code "115") (name "POWERSC_+X_NEW") (class "Default")
      (node (ref "C101") (pin "P$27") (pinfunction "27_P$27") (pintype "passive"))
      (node (ref "SP1") (pin "8") (pinfunction "8_8") (pintype "passive"))
      (node (ref "SP1") (pin "9") (pinfunction "9_9") (pintype "passive"))
    )
    (net (code "116") (name "POWERSC_+Y_NEW") (class "Default")
      (node (ref "C101") (pin "P$37") (pinfunction "37_P$37") (pintype "passive"))
      (node (ref "SP3") (pin "8") (pinfunction "8_8") (pintype "passive"))
      (node (ref "SP3") (pin "9") (pinfunction "9_9") (pintype "passive"))
    )
    (net (code "117") (name "POWERSC_-X_NEW") (class "Default")
      (node (ref "C101") (pin "P$31") (pinfunction "31_P$31") (pintype "passive"))
      (node (ref "SP2") (pin "8") (pinfunction "8_8") (pintype "passive"))
      (node (ref "SP2") (pin "9") (pinfunction "9_9") (pintype "passive"))
    )
    (net (code "118") (name "POWERSC_-Y_NEW") (class "Default")
      (node (ref "C101") (pin "P$21") (pinfunction "21_P$21") (pintype "passive"))
      (node (ref "SP4") (pin "8") (pinfunction "8_8") (pintype "passive"))
      (node (ref "SP4") (pin "9") (pinfunction "9_9") (pintype "passive"))
    )
    (net (code "119") (name "POWERSC_-Z_NEW") (class "Default")
      (node (ref "C101") (pin "P$33") (pinfunction "33_P$33") (pintype "passive"))
      (node (ref "SP5") (pin "8") (pinfunction "8_8") (pintype "passive"))
      (node (ref "SP5") (pin "9") (pinfunction "9_9") (pintype "passive"))
    )
    (net (code "120") (name "PROG1") (class "Default")
      (node (ref "C101") (pin "P$1") (pinfunction "1_P$1") (pintype "passive"))
      (node (ref "C102") (pin "P$1") (pinfunction "1_P$1") (pintype "passive"))
    )
    (net (code "121") (name "PROG2") (class "Default")
      (node (ref "C101") (pin "P$2") (pinfunction "2_P$2") (pintype "passive"))
      (node (ref "C102") (pin "P$2") (pinfunction "2_P$2") (pintype "passive"))
    )
    (net (code "122") (name "PROG3") (class "Default")
      (node (ref "C101") (pin "P$3") (pinfunction "3_P$3") (pintype "passive"))
      (node (ref "C102") (pin "P$3") (pinfunction "3_P$3") (pintype "passive"))
    )
    (net (code "123") (name "PROG4") (class "Default")
      (node (ref "C101") (pin "P$4") (pinfunction "4_P$4") (pintype "passive"))
      (node (ref "C102") (pin "P$4") (pinfunction "4_P$4") (pintype "passive"))
    )
    (net (code "124") (name "PROG5") (class "Default")
      (node (ref "C101") (pin "P$5") (pinfunction "5_P$5") (pintype "passive"))
      (node (ref "C102") (pin "P$5") (pinfunction "5_P$5") (pintype "passive"))
    )
    (net (code "125") (name "PROG6") (class "Default")
      (node (ref "C101") (pin "P$6") (pinfunction "6_P$6") (pintype "passive"))
      (node (ref "C102") (pin "P$6") (pinfunction "6_P$6") (pintype "passive"))
    )
    (net (code "126") (name "RAW_POWER") (class "Default")
      (node (ref "C101") (pin "P$29") (pinfunction "29_P$29") (pintype "passive"))
      (node (ref "C101") (pin "P$30") (pinfunction "30_P$30") (pintype "passive"))
      (node (ref "C102") (pin "P$29") (pinfunction "29_P$29") (pintype "passive"))
      (node (ref "C102") (pin "P$30") (pinfunction "30_P$30") (pintype "passive"))
      (node (ref "R5") (pin "1") (pinfunction "1_1") (pintype "passive"))
      (node (ref "R7") (pin "1") (pinfunction "1_1") (pintype "passive"))
    )
    (net (code "127") (name "SUP5V0") (class "Default")
      (node (ref "C101") (pin "P$15") (pinfunction "15_P$15") (pintype "passive"))
      (node (ref "C101") (pin "P$16") (pinfunction "16_P$16") (pintype "passive"))
      (node (ref "C102") (pin "P$15") (pinfunction "15_P$15") (pintype "passive"))
      (node (ref "C102") (pin "P$16") (pinfunction "16_P$16") (pintype "passive"))
      (node (ref "C103") (pin "P$15") (pinfunction "15_P$15") (pintype "passive"))
      (node (ref "C103") (pin "P$16") (pinfunction "16_P$16") (pintype "passive"))
      (node (ref "C104") (pin "P$15") (pinfunction "15_P$15") (pintype "passive"))
      (node (ref "C104") (pin "P$16") (pinfunction "16_P$16") (pintype "passive"))
      (node (ref "C105") (pin "P$15") (pinfunction "15_P$15") (pintype "passive"))
      (node (ref "C105") (pin "P$16") (pinfunction "16_P$16") (pintype "passive"))
      (node (ref "C106") (pin "P$15") (pinfunction "15_P$15") (pintype "passive"))
      (node (ref "C106") (pin "P$16") (pinfunction "16_P$16") (pintype "passive"))
    )
    (net (code "128") (name "SUP_3V3_1") (class "Default")
      (node (ref "C101") (pin "P$49") (pinfunction "49_P$49") (pintype "passive"))
      (node (ref "C101") (pin "P$50") (pinfunction "50_P$50") (pintype "passive"))
      (node (ref "C102") (pin "P$49") (pinfunction "49_P$49") (pintype "passive"))
      (node (ref "C102") (pin "P$50") (pinfunction "50_P$50") (pintype "passive"))
      (node (ref "C103") (pin "P$49") (pinfunction "49_P$49") (pintype "passive"))
      (node (ref "C103") (pin "P$50") (pinfunction "50_P$50") (pintype "passive"))
      (node (ref "C104") (pin "P$49") (pinfunction "49_P$49") (pintype "passive"))
      (node (ref "C104") (pin "P$50") (pinfunction "50_P$50") (pintype "passive"))
      (node (ref "C105") (pin "P$49") (pinfunction "49_P$49") (pintype "passive"))
      (node (ref "C105") (pin "P$50") (pinfunction "50_P$50") (pintype "passive"))
      (node (ref "C106") (pin "P$49") (pinfunction "49_P$49") (pintype "passive"))
      (node (ref "C106") (pin "P$50") (pinfunction "50_P$50") (pintype "passive"))
      (node (ref "C7") (pin "1") (pinfunction "1_1") (pintype "passive"))
      (node (ref "SP1") (pin "2") (pinfunction "2_2") (pintype "passive"))
      (node (ref "SP2") (pin "2") (pinfunction "2_2") (pintype "passive"))
      (node (ref "SP3") (pin "2") (pinfunction "2_2") (pintype "passive"))
      (node (ref "SP4") (pin "2") (pinfunction "2_2") (pintype "passive"))
      (node (ref "SP5") (pin "2") (pinfunction "2_2") (pintype "passive"))
      (node (ref "T1") (pin "5") (pinfunction "~_5") (pintype "passive"))
      (node (ref "T1") (pin "8") (pinfunction "+VS_8") (pintype "power_in"))
    )
    (net (code "129") (name "SUP_3V3_2") (class "Default")
      (node (ref "C101") (pin "P$25") (pinfunction "25_P$25") (pintype "passive"))
      (node (ref "C101") (pin "P$26") (pinfunction "26_P$26") (pintype "passive"))
      (node (ref "C102") (pin "P$25") (pinfunction "25_P$25") (pintype "passive"))
      (node (ref "C102") (pin "P$26") (pinfunction "26_P$26") (pintype "passive"))
      (node (ref "C103") (pin "P$25") (pinfunction "25_P$25") (pintype "passive"))
      (node (ref "C103") (pin "P$26") (pinfunction "26_P$26") (pintype "passive"))
      (node (ref "C104") (pin "P$25") (pinfunction "25_P$25") (pintype "passive"))
      (node (ref "C104") (pin "P$26") (pinfunction "26_P$26") (pintype "passive"))
      (node (ref "C105") (pin "P$25") (pinfunction "25_P$25") (pintype "passive"))
      (node (ref "C105") (pin "P$26") (pinfunction "26_P$26") (pintype "passive"))
      (node (ref "C106") (pin "P$25") (pinfunction "25_P$25") (pintype "passive"))
      (node (ref "C106") (pin "P$26") (pinfunction "26_P$26") (pintype "passive"))
    )
    (net (code "130") (name "SUP_UNREG_1") (class "Default")
      (node (ref "C101") (pin "P$23") (pinfunction "23_P$23") (pintype "passive"))
      (node (ref "C101") (pin "P$24") (pinfunction "24_P$24") (pintype "passive"))
      (node (ref "C102") (pin "P$23") (pinfunction "23_P$23") (pintype "passive"))
      (node (ref "C102") (pin "P$24") (pinfunction "24_P$24") (pintype "passive"))
      (node (ref "C103") (pin "P$23") (pinfunction "23_P$23") (pintype "passive"))
      (node (ref "C103") (pin "P$24") (pinfunction "24_P$24") (pintype "passive"))
      (node (ref "C104") (pin "P$23") (pinfunction "23_P$23") (pintype "passive"))
      (node (ref "C104") (pin "P$24") (pinfunction "24_P$24") (pintype "passive"))
      (node (ref "C105") (pin "P$23") (pinfunction "23_P$23") (pintype "passive"))
      (node (ref "C105") (pin "P$24") (pinfunction "24_P$24") (pintype "passive"))
      (node (ref "C106") (pin "P$23") (pinfunction "23_P$23") (pintype "passive"))
      (node (ref "C106") (pin "P$24") (pinfunction "24_P$24") (pintype "passive"))
    )
    (net (code "131") (name "SUP_UNREG_2") (class "Default")
      (node (ref "C101") (pin "P$35") (pinfunction "35_P$35") (pintype "passive"))
      (node (ref "C101") (pin "P$36") (pinfunction "36_P$36") (pintype "passive"))
      (node (ref "C102") (pin "P$35") (pinfunction "35_P$35") (pintype "passive"))
      (node (ref "C102") (pin "P$36") (pinfunction "36_P$36") (pintype "passive"))
      (node (ref "C103") (pin "P$35") (pinfunction "35_P$35") (pintype "passive"))
      (node (ref "C103") (pin "P$36") (pinfunction "36_P$36") (pintype "passive"))
      (node (ref "C104") (pin "P$35") (pinfunction "35_P$35") (pintype "passive"))
      (node (ref "C104") (pin "P$36") (pinfunction "36_P$36") (pintype "passive"))
      (node (ref "C105") (pin "P$35") (pinfunction "35_P$35") (pintype "passive"))
      (node (ref "C105") (pin "P$36") (pinfunction "36_P$36") (pintype "passive"))
      (node (ref "C106") (pin "P$35") (pinfunction "35_P$35") (pintype "passive"))
      (node (ref "C106") (pin "P$36") (pinfunction "36_P$36") (pintype "passive"))
    )
    (net (code "132") (name "TEMP1_+X_NEW") (class "Default")
      (node (ref "C101") (pin "P$28") (pinfunction "28_P$28") (pintype "passive"))
      (node (ref "SP1") (pin "10") (pinfunction "10_10") (pintype "passive"))
    )
    (net (code "133") (name "TEMP2_-Y_NEW") (class "Default")
      (node (ref "C101") (pin "P$22") (pinfunction "22_P$22") (pintype "passive"))
      (node (ref "SP4") (pin "10") (pinfunction "10_10") (pintype "passive"))
    )
    (net (code "134") (name "TEMP3_-Z_NEW") (class "Default")
      (node (ref "C101") (pin "P$34") (pinfunction "34_P$34") (pintype "passive"))
      (node (ref "SP5") (pin "10") (pinfunction "10_10") (pintype "passive"))
    )
    (net (code "135") (name "TEMP4_+Y_NEW") (class "Default")
      (node (ref "C101") (pin "P$38") (pinfunction "38_P$38") (pintype "passive"))
      (node (ref "SP3") (pin "10") (pinfunction "10_10") (pintype "passive"))
    )
    (net (code "136") (name "TEMP5_-X_NEW") (class "Default")
      (node (ref "C101") (pin "P$32") (pinfunction "32_P$32") (pintype "passive"))
      (node (ref "SP2") (pin "10") (pinfunction "10_10") (pintype "passive"))
    )
    (net (code "137") (name "unconnected-(C105-21-PadP$21)") (class "Default")
      (node (ref "C105") (pin "P$21") (pinfunction "21_P$21") (pintype "passive"))
    )
    (net (code "138") (name "unconnected-(C105-22-PadP$22)") (class "Default")
      (node (ref "C105") (pin "P$22") (pinfunction "22_P$22") (pintype "passive"))
    )
    (net (code "139") (name "unconnected-(SP1-Pad3)") (class "Default")
      (node (ref "SP1") (pin "3") (pinfunction "3_3") (pintype "passive"))
    )
    (net (code "140") (name "unconnected-(SP1-Pad4)") (class "Default")
      (node (ref "SP1") (pin "4") (pinfunction "4_4") (pintype "passive"))
    )
    (net (code "141") (name "unconnected-(SP1-Pad5)") (class "Default")
      (node (ref "SP1") (pin "5") (pinfunction "5_5") (pintype "passive"))
    )
    (net (code "142") (name "unconnected-(SP1-Pad6)") (class "Default")
      (node (ref "SP1") (pin "6") (pinfunction "6_6") (pintype "passive"))
    )
    (net (code "143") (name "unconnected-(SP1-Pad7)") (class "Default")
      (node (ref "SP1") (pin "7") (pinfunction "7_7") (pintype "passive"))
    )
    (net (code "144") (name "unconnected-(SP1-Pad11)") (class "Default")
      (node (ref "SP1") (pin "11") (pinfunction "11_11") (pintype "passive"))
    )
    (net (code "145") (name "unconnected-(SP2-Pad3)") (class "Default")
      (node (ref "SP2") (pin "3") (pinfunction "3_3") (pintype "passive"))
    )
    (net (code "146") (name "unconnected-(SP2-Pad4)") (class "Default")
      (node (ref "SP2") (pin "4") (pinfunction "4_4") (pintype "passive"))
    )
    (net (code "147") (name "unconnected-(SP2-Pad5)") (class "Default")
      (node (ref "SP2") (pin "5") (pinfunction "5_5") (pintype "passive"))
    )
    (net (code "148") (name "unconnected-(SP2-Pad6)") (class "Default")
      (node (ref "SP2") (pin "6") (pinfunction "6_6") (pintype "passive"))
    )
    (net (code "149") (name "unconnected-(SP2-Pad7)") (class "Default")
      (node (ref "SP2") (pin "7") (pinfunction "7_7") (pintype "passive"))
    )
    (net (code "150") (name "unconnected-(SP2-Pad11)") (class "Default")
      (node (ref "SP2") (pin "11") (pinfunction "11_11") (pintype "passive"))
    )
    (net (code "151") (name "unconnected-(SP3-Pad3)") (class "Default")
      (node (ref "SP3") (pin "3") (pinfunction "3_3") (pintype "passive"))
    )
    (net (code "152") (name "unconnected-(SP3-Pad4)") (class "Default")
      (node (ref "SP3") (pin "4") (pinfunction "4_4") (pintype "passive"))
    )
    (net (code "153") (name "unconnected-(SP3-Pad5)") (class "Default")
      (node (ref "SP3") (pin "5") (pinfunction "5_5") (pintype "passive"))
    )
    (net (code "154") (name "unconnected-(SP3-Pad6)") (class "Default")
      (node (ref "SP3") (pin "6") (pinfunction "6_6") (pintype "passive"))
    )
    (net (code "155") (name "unconnected-(SP3-Pad7)") (class "Default")
      (node (ref "SP3") (pin "7") (pinfunction "7_7") (pintype "passive"))
    )
    (net (code "156") (name "unconnected-(SP3-Pad11)") (class "Default")
      (node (ref "SP3") (pin "11") (pinfunction "11_11") (pintype "passive"))
    )
    (net (code "157") (name "unconnected-(SP4-Pad3)") (class "Default")
      (node (ref "SP4") (pin "3") (pinfunction "3_3") (pintype "passive"))
    )
    (net (code "158") (name "unconnected-(SP4-Pad4)") (class "Default")
      (node (ref "SP4") (pin "4") (pinfunction "4_4") (pintype "passive"))
    )
    (net (code "159") (name "unconnected-(SP4-Pad5)") (class "Default")
      (node (ref "SP4") (pin "5") (pinfunction "5_5") (pintype "passive"))
    )
    (net (code "160") (name "unconnected-(SP4-Pad11)") (class "Default")
      (node (ref "SP4") (pin "11") (pinfunction "11_11") (pintype "passive"))
    )
    (net (code "161") (name "unconnected-(SP5-Pad3)") (class "Default")
      (node (ref "SP5") (pin "3") (pinfunction "3_3") (pintype "passive"))
    )
    (net (code "162") (name "unconnected-(SP5-Pad4)") (class "Default")
      (node (ref "SP5") (pin "4") (pinfunction "4_4") (pintype "passive"))
    )
    (net (code "163") (name "unconnected-(SP5-Pad5)") (class "Default")
      (node (ref "SP5") (pin "5") (pinfunction "5_5") (pintype "passive"))
    )
    (net (code "164") (name "unconnected-(SP5-Pad11)") (class "Default")
      (node (ref "SP5") (pin "11") (pinfunction "11_11") (pintype "passive"))
    )
    (net (code "165") (name "unconnected-(T1-NC-Pad7)") (class "Default")
      (node (ref "T1") (pin "7") (pinfunction "NC_7") (pintype "passive"))
    )
    (net (code "166") (name "unconnected-(T1-NC_2-Pad2)") (class "Default")
      (node (ref "T1") (pin "2") (pinfunction "NC_2_2") (pintype "passive"))
    )
    (net (code "167") (name "unconnected-(T1-NC_3-Pad3)") (class "Default")
      (node (ref "T1") (pin "3") (pinfunction "NC_3_3") (pintype "passive"))
    )
    (net (code "168") (name "unconnected-(T1-NC_4-Pad6)") (class "Default")
      (node (ref "T1") (pin "6") (pinfunction "NC_4_6") (pintype "passive"))
    )
  )
)
